# src.net
KiCad netlist of a schematic drawn in EasyEDA
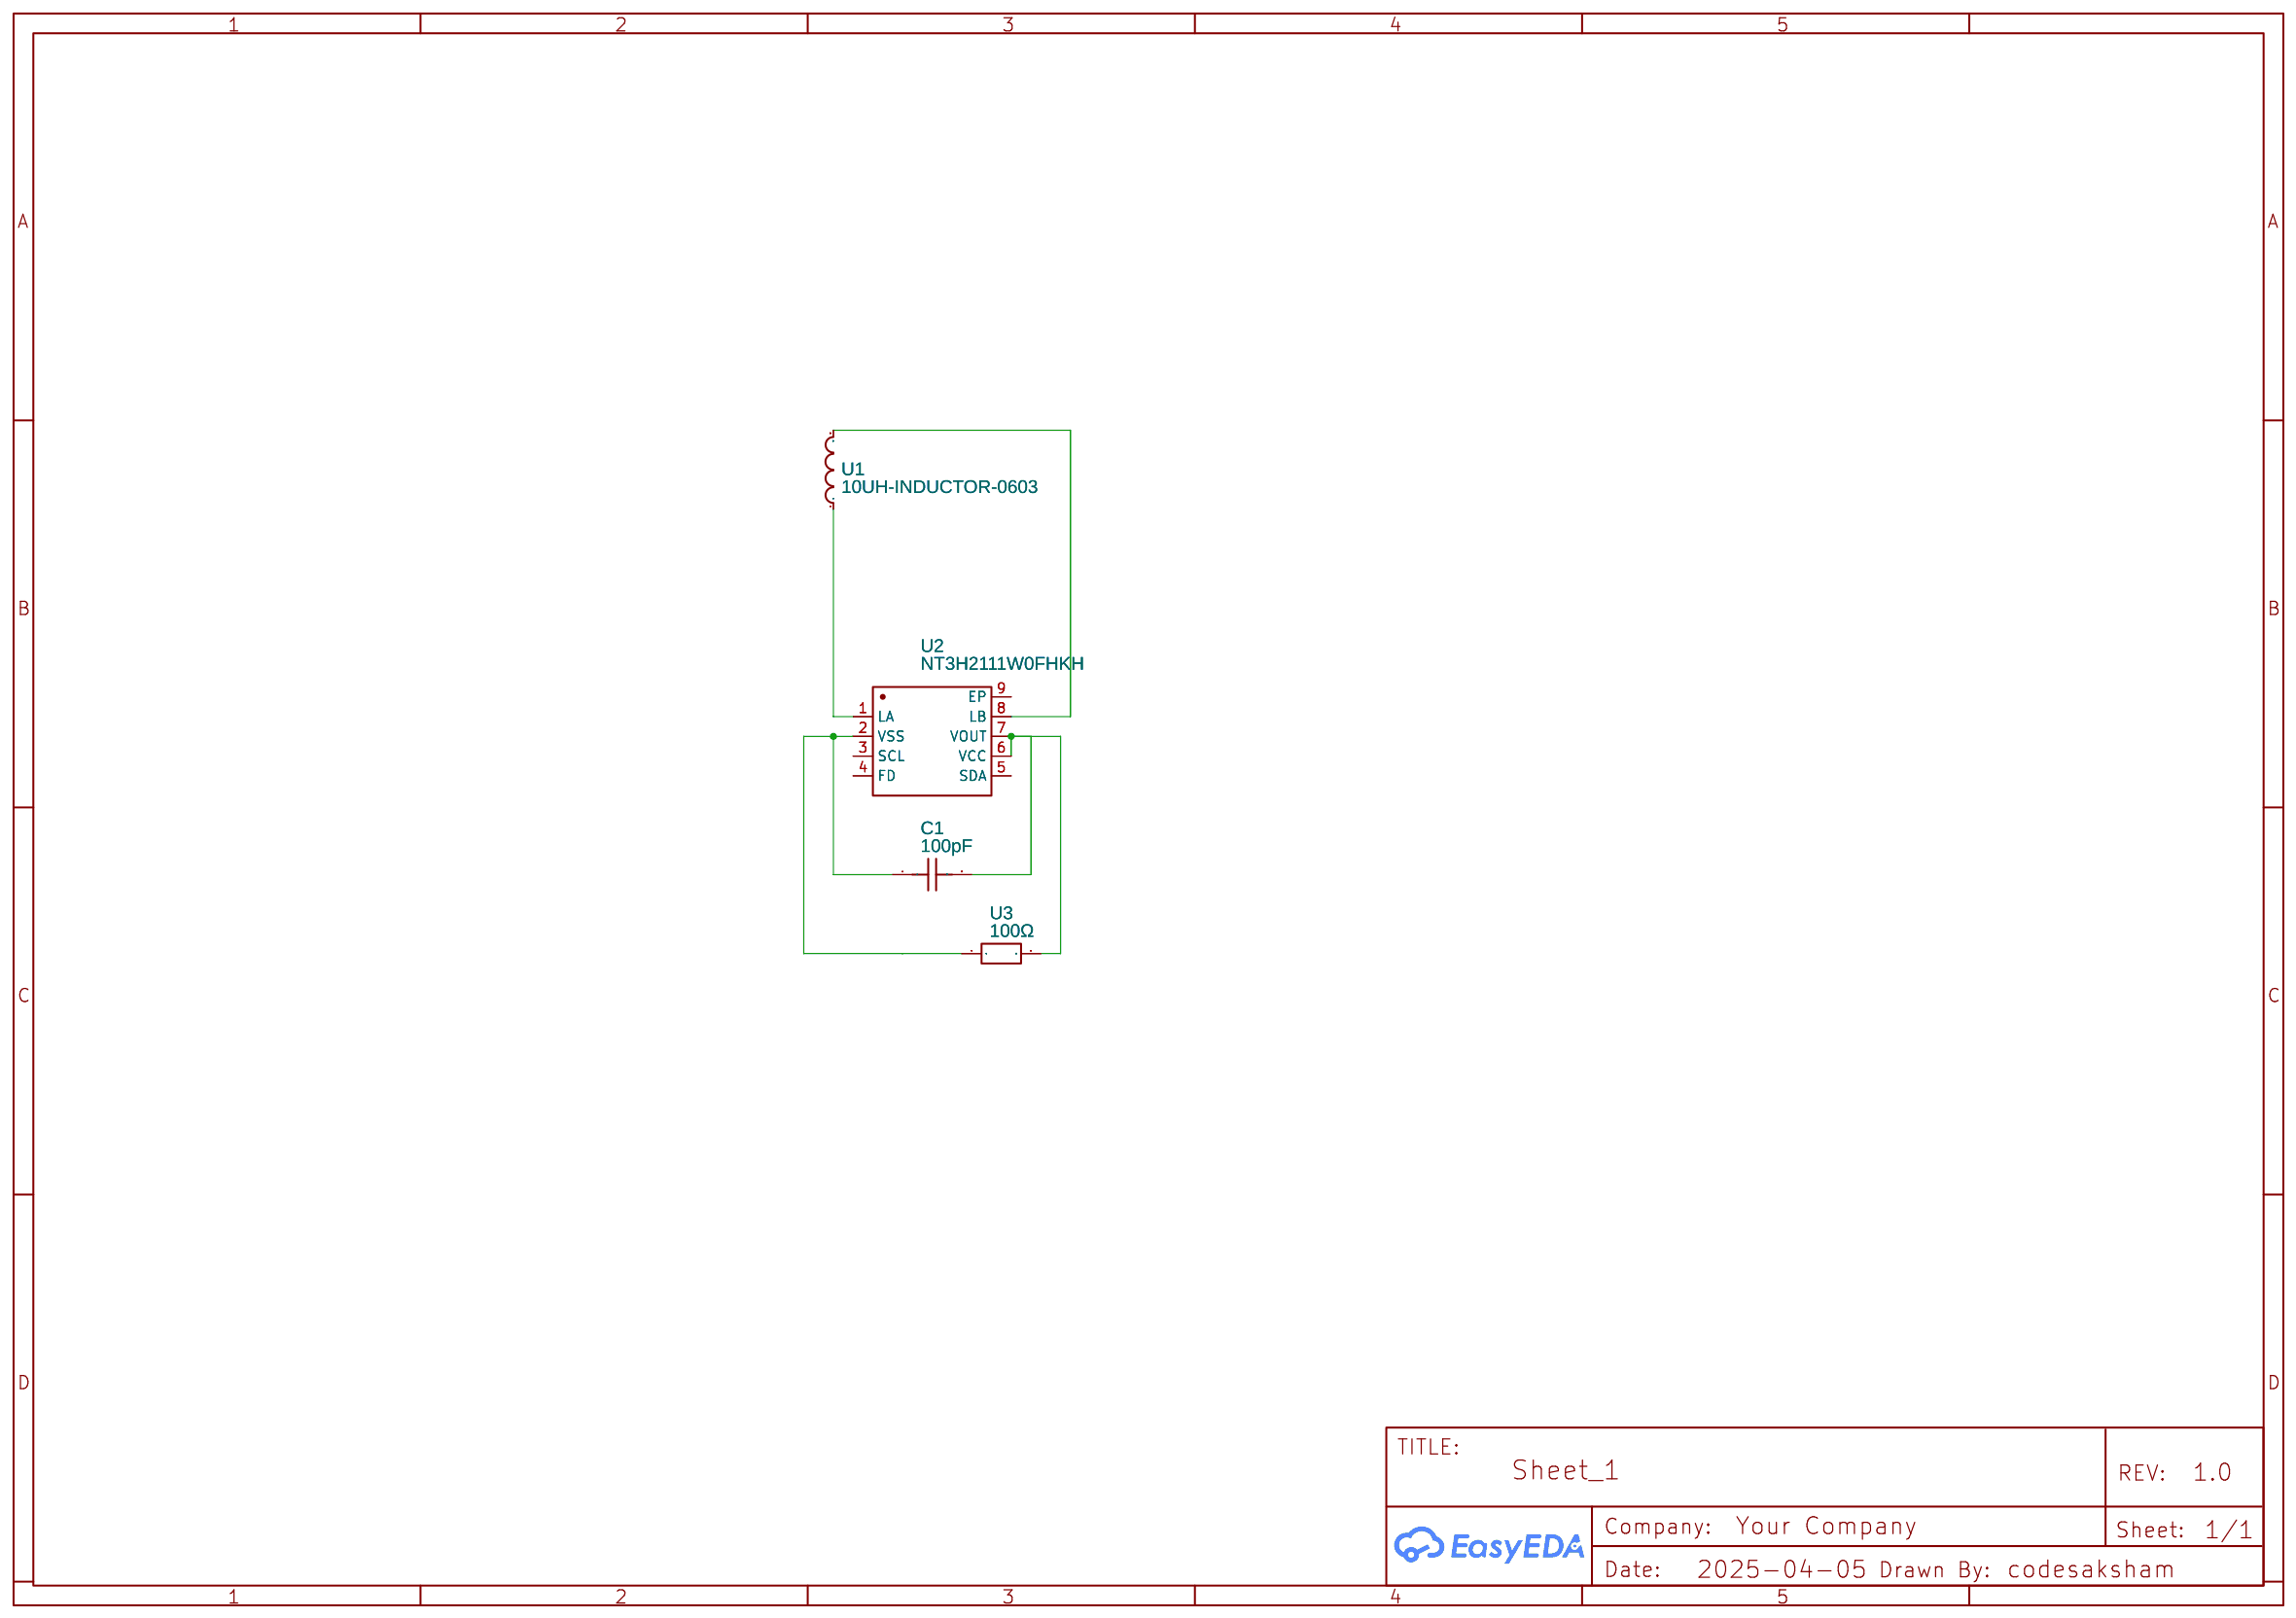
[diagram p0: schematic sheet]

(export (version "E")
  (design (tool "Eeschema 10.0.6"))
  (components
    (comp (ref "C1")
      (value "100pF")
      (fields (field (name "Manufacturer Part") "C0402X6S1A101K020BC") (field (name "Manufacturer") "TDK"))
      (libsource (lib "") (part "C0402X6S1A101K020BC"))
    )
    (comp (ref "U1")
      (value "10UH-INDUCTOR-0603")
      (fields (field (name "Manufacturer Part") "10uH-INDUCTOR-0603"))
      (libsource (lib "") (part "10UH-INDUCTOR-0603"))
    )
    (comp (ref "U2")
      (value "NT3H2111W0FHKH")
      (fields (field (name "Manufacturer") "NXP(恩智浦)"))
      (libsource (lib "") (part "NT3H2111W0FHKH"))
    )
    (comp (ref "U3")
      (value "100Ω")
      (fields
        (field (name "Manufacturer Part") "M55342H03B100DRT5")
        (field (name "Manufacturer") "VISHAY(威世)")
      )
      (libsource (lib "") (part "M55342H03B100DRT5"))
    )
  )
  (nets
    (net (code "1") (name "Net-(U2-LA)") (class "Default")
      (node (ref "U1") (pin "1") (pinfunction "1_1") (pintype "unspecified"))
      (node (ref "U2") (pin "1") (pinfunction "LA_1") (pintype "unspecified"))
    )
    (net (code "2") (name "Net-(U2-LB)") (class "Default")
      (node (ref "U1") (pin "2") (pinfunction "2_2") (pintype "unspecified"))
      (node (ref "U2") (pin "8") (pinfunction "LB_8") (pintype "unspecified"))
    )
    (net (code "3") (name "Net-(U2-VCC)") (class "Default")
      (node (ref "C1") (pin "2") (pinfunction "2_2") (pintype "unspecified"))
      (node (ref "U2") (pin "6") (pinfunction "VCC_6") (pintype "unspecified"))
      (node (ref "U2") (pin "7") (pinfunction "VOUT_7") (pintype "unspecified"))
      (node (ref "U3") (pin "2") (pinfunction "2_2") (pintype "unspecified"))
    )
    (net (code "4") (name "Net-(U2-VSS)") (class "Default")
      (node (ref "C1") (pin "1") (pinfunction "1_1") (pintype "unspecified"))
      (node (ref "U2") (pin "2") (pinfunction "VSS_2") (pintype "unspecified"))
      (node (ref "U3") (pin "1") (pinfunction "1_1") (pintype "unspecified"))
    )
    (net (code "5") (name "unconnected-(U2-EP-Pad9)") (class "Default")
      (node (ref "U2") (pin "9") (pinfunction "EP_9") (pintype "unspecified"))
    )
    (net (code "6") (name "unconnected-(U2-FD-Pad4)") (class "Default")
      (node (ref "U2") (pin "4") (pinfunction "FD_4") (pintype "unspecified"))
    )
    (net (code "7") (name "unconnected-(U2-SCL-Pad3)") (class "Default")
      (node (ref "U2") (pin "3") (pinfunction "SCL_3") (pintype "unspecified"))
    )
    (net (code "8") (name "unconnected-(U2-SDA-Pad5)") (class "Default")
      (node (ref "U2") (pin "5") (pinfunction "SDA_5") (pintype "unspecified"))
    )
  )
)
